# EncoderDaughter.net
KiCad netlist of a schematic drawn in Altium Designer
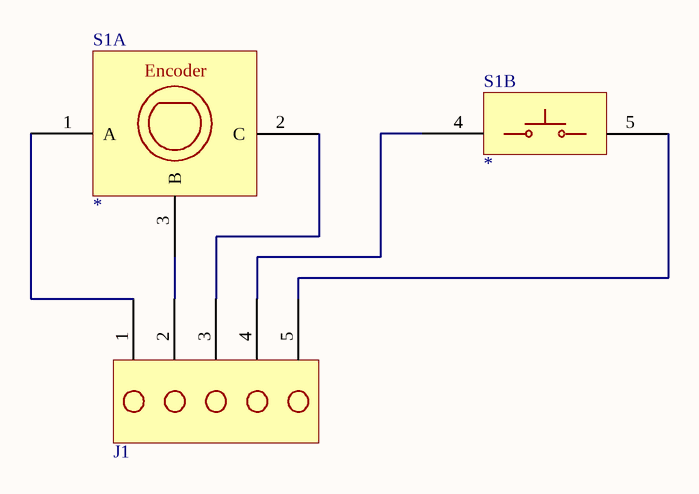
[diagram p0: EncoderDaughter.SchDoc]

(export (version "E")
  (design (tool "Eeschema 10.0.6"))
  (components
    (comp (ref "J1")
      (value "J_RIBBCONN_RIBBCONN")
      (footprint "RIBBCONN")
      (libsource (lib "SeniorProject") (part "J_RIBBCONN_RIBBCONN"))
    )
    (comp (ref "S1")
      (value "S_QUADENC_PEC11-4215F-S24")
      (footprint "PEC11-4215F-S24")
      (fields (field (name "PARTNUMBER") "*"))
      (libsource (lib "SeniorProject") (part "S_QUADENC_PEC11-4215F-S24"))
    )
  )
  (nets
    (net (code "1") (name "Net-(J1-Pad4)") (class "Default")
      (node (ref "J1") (pin "4") (pintype "passive"))
      (node (ref "S1") (pin "4") (pintype "passive"))
    )
    (net (code "2") (name "Net-(J1-Pad5)") (class "Default")
      (node (ref "J1") (pin "5") (pinfunction "5_5") (pintype "passive"))
      (node (ref "S1") (pin "5") (pintype "passive"))
    )
    (net (code "3") (name "Net-(S1A-A)") (class "Default")
      (node (ref "J1") (pin "1") (pintype "passive"))
      (node (ref "S1") (pin "1") (pinfunction "A_1") (pintype "passive"))
    )
    (net (code "4") (name "Net-(S1A-B)") (class "Default")
      (node (ref "J1") (pin "2") (pintype "passive"))
      (node (ref "S1") (pin "3") (pinfunction "B_3") (pintype "passive"))
    )
    (net (code "5") (name "Net-(S1A-C)") (class "Default")
      (node (ref "J1") (pin "3") (pintype "passive"))
      (node (ref "S1") (pin "2") (pinfunction "C_2") (pintype "passive"))
    )
  )
)
